# pavapro3c.net
KiCad netlist of a schematic drawn in EAGLE
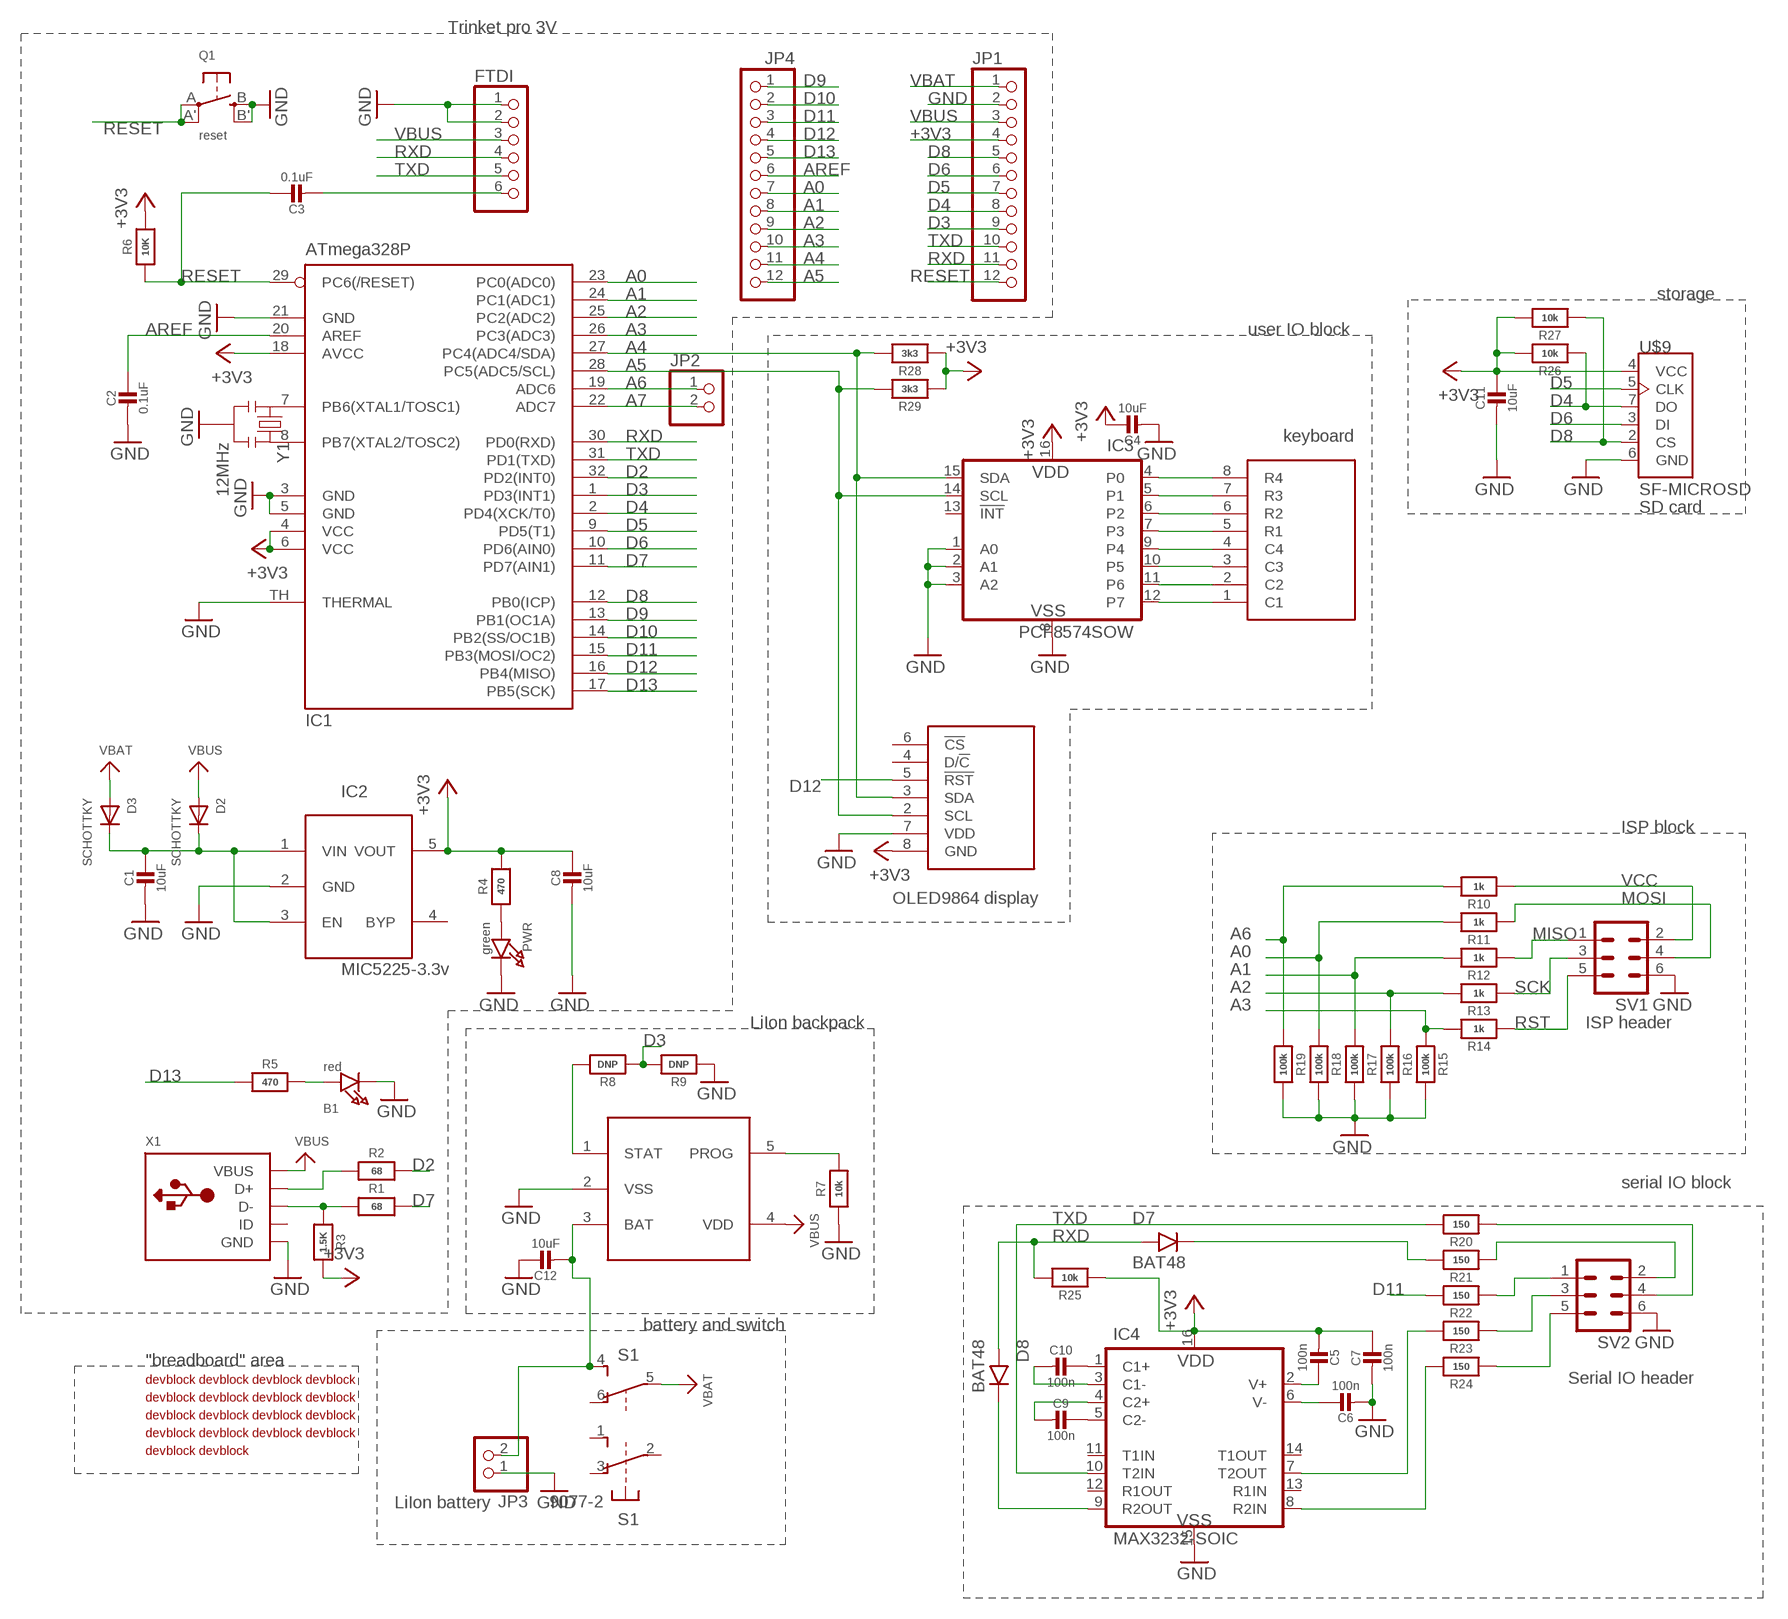
[diagram p0: schematic, sheet 1]

(export (version "E")
  (design (tool "Eeschema 10.0.6"))
  (components
    (comp (ref "B1")
      (value "red")
      (footprint "eagle-import:CHIPLED_0805_NOOUTLINE")
      (libsource (lib "eagle-import") (part "LED0805_NOOUTLINE"))
    )
    (comp (ref "C1")
      (value "10uF")
      (footprint "eagle-import:0805-NO")
      (libsource (lib "eagle-import") (part "CAP_CERAMIC0805-NOOUTLINE"))
    )
    (comp (ref "C2")
      (value "0.1uF")
      (footprint "eagle-import:_0805MP")
      (libsource (lib "eagle-import") (part "CAP_CERAMIC_0805MP"))
    )
    (comp (ref "C3")
      (value "0.1uF")
      (footprint "eagle-import:0805-NO")
      (libsource (lib "eagle-import") (part "CAP_CERAMIC0805-NOOUTLINE"))
    )
    (comp (ref "C4")
      (value "10uF")
      (footprint "eagle-import:0805-NO")
      (libsource (lib "eagle-import") (part "CAP_CERAMIC0805-NOOUTLINE"))
    )
    (comp (ref "C5")
      (value "100n")
      (footprint "eagle-import:0805-NO")
      (libsource (lib "eagle-import") (part "CAP_CERAMIC0805-NOOUTLINE"))
    )
    (comp (ref "C6")
      (value "100n")
      (footprint "eagle-import:0805-NO")
      (libsource (lib "eagle-import") (part "CAP_CERAMIC0805-NOOUTLINE"))
    )
    (comp (ref "C7")
      (value "100n")
      (footprint "eagle-import:0805-NO")
      (libsource (lib "eagle-import") (part "CAP_CERAMIC0805-NOOUTLINE"))
    )
    (comp (ref "C8")
      (value "10uF")
      (footprint "eagle-import:0805-NO")
      (libsource (lib "eagle-import") (part "CAP_CERAMIC0805-NOOUTLINE"))
    )
    (comp (ref "C9")
      (value "100n")
      (footprint "eagle-import:0805-NO")
      (libsource (lib "eagle-import") (part "CAP_CERAMIC0805-NOOUTLINE"))
    )
    (comp (ref "C10")
      (value "100n")
      (footprint "eagle-import:0805-NO")
      (libsource (lib "eagle-import") (part "CAP_CERAMIC0805-NOOUTLINE"))
    )
    (comp (ref "C11")
      (value "10uF")
      (footprint "eagle-import:0805-NO")
      (libsource (lib "eagle-import") (part "CAP_CERAMIC0805-NOOUTLINE"))
    )
    (comp (ref "C12")
      (value "10uF")
      (footprint "eagle-import:0805-NO")
      (libsource (lib "eagle-import") (part "CAP_CERAMIC0805-NOOUTLINE"))
    )
    (comp (ref "D2")
      (value "SCHOTTKY")
      (footprint "eagle-import:ADAFRUIT_SOD-123FL")
      (libsource (lib "eagle-import") (part "ADAFRUIT_DIODE_SOD-123FL"))
    )
    (comp (ref "D3")
      (value "SCHOTTKY")
      (footprint "eagle-import:ADAFRUIT_SOD-123FL")
      (libsource (lib "eagle-import") (part "ADAFRUIT_DIODE_SOD-123FL"))
    )
    (comp (ref "D7")
      (value "BAT48")
      (footprint "eagle-import:SOD-80")
      (libsource (lib "eagle-import") (part "1N4148SOD"))
    )
    (comp (ref "D8")
      (value "BAT48")
      (footprint "eagle-import:SOD-80")
      (libsource (lib "eagle-import") (part "1N4148SOD"))
    )
    (comp (ref "FTDI")
      (value "ADAFRUIT_PINHD-1X6CB")
      (footprint "eagle-import:ADAFRUIT_1X06-CLEANBIG")
      (libsource (lib "eagle-import") (part "ADAFRUIT_PINHD-1X6CB"))
    )
    (comp (ref "IC1")
      (value "ATmega328P")
      (footprint "eagle-import:MLF32-TH")
      (fields (field (name "MPN") "ATMEGA88PA-MU"))
      (libsource (lib "eagle-import") (part "MEGA8-MI"))
    )
    (comp (ref "IC2")
      (value "MIC5225-3.3v")
      (footprint "eagle-import:SOT23-5L")
      (libsource (lib "eagle-import") (part "LP298XS"))
    )
    (comp (ref "IC3")
      (value "PCF8574SOW")
      (footprint "eagle-import:SO-16DW")
      (libsource (lib "eagle-import") (part "PCF8574SOW"))
    )
    (comp (ref "IC4")
      (value "MAX3232-SOIC")
      (footprint "eagle-import:SO-16")
      (libsource (lib "eagle-import") (part "MAX3232-SOIC"))
    )
    (comp (ref "JP1")
      (value "ADAFRUIT_PINHD-1X12-CB")
      (footprint "eagle-import:ADAFRUIT_1X12-CB")
      (libsource (lib "eagle-import") (part "ADAFRUIT_PINHD-1X12-CB"))
    )
    (comp (ref "JP2")
      (value "HEADER-1X2ROUND")
      (footprint "eagle-import:1X02_ROUND")
      (libsource (lib "eagle-import") (part "HEADER-1X2ROUND"))
    )
    (comp (ref "JP3")
      (value "PINHD-1X02_2.54-90°")
      (footprint "eagle-import:1X02_90")
      (libsource (lib "eagle-import") (part "PINHD-1X02_2.54-90°"))
    )
    (comp (ref "JP4")
      (value "ADAFRUIT_PINHD-1X12-CB")
      (footprint "eagle-import:ADAFRUIT_1X12-CB")
      (libsource (lib "eagle-import") (part "ADAFRUIT_PINHD-1X12-CB"))
    )
    (comp (ref "PWR")
      (value "green")
      (footprint "eagle-import:CHIPLED_0805_NOOUTLINE")
      (libsource (lib "eagle-import") (part "LED0805_NOOUTLINE"))
    )
    (comp (ref "Q1")
      (value "reset")
      (footprint "eagle-import:BTN_KMR2_4.6X2.8")
      (libsource (lib "eagle-import") (part "SWITCH_TACT_SMT4.6X2.8"))
    )
    (comp (ref "R1")
      (value "68")
      (footprint "eagle-import:0603-NO")
      (libsource (lib "eagle-import") (part "RESISTOR_0603_NOOUT"))
    )
    (comp (ref "R2")
      (value "68")
      (footprint "eagle-import:0603-NO")
      (libsource (lib "eagle-import") (part "RESISTOR_0603_NOOUT"))
    )
    (comp (ref "R3")
      (value "1.5K")
      (footprint "eagle-import:0603-NO")
      (libsource (lib "eagle-import") (part "RESISTOR_0603_NOOUT"))
    )
    (comp (ref "R4")
      (value "470")
      (footprint "eagle-import:0603-NO")
      (libsource (lib "eagle-import") (part "RESISTOR_0603_NOOUT"))
    )
    (comp (ref "R5")
      (value "470")
      (footprint "eagle-import:0603-NO")
      (libsource (lib "eagle-import") (part "RESISTOR_0603_NOOUT"))
    )
    (comp (ref "R6")
      (value "10K")
      (footprint "eagle-import:0805-NO")
      (libsource (lib "eagle-import") (part "RESISTOR0805_NOOUTLINE"))
    )
    (comp (ref "R7")
      (value "10k")
      (footprint "eagle-import:_0805")
      (libsource (lib "eagle-import") (part "RESISTOR_0805"))
    )
    (comp (ref "R8")
      (value "DNP")
      (footprint "eagle-import:_0805")
      (libsource (lib "eagle-import") (part "RESISTOR_0805"))
    )
    (comp (ref "R9")
      (value "DNP")
      (footprint "eagle-import:_0805")
      (libsource (lib "eagle-import") (part "RESISTOR_0805"))
    )
    (comp (ref "R10")
      (value "1k")
      (footprint "eagle-import:_0805")
      (libsource (lib "eagle-import") (part "RESISTOR_0805"))
    )
    (comp (ref "R11")
      (value "1k")
      (footprint "eagle-import:_0805")
      (libsource (lib "eagle-import") (part "RESISTOR_0805"))
    )
    (comp (ref "R12")
      (value "1k")
      (footprint "eagle-import:_0805")
      (libsource (lib "eagle-import") (part "RESISTOR_0805"))
    )
    (comp (ref "R13")
      (value "1k")
      (footprint "eagle-import:_0805")
      (libsource (lib "eagle-import") (part "RESISTOR_0805"))
    )
    (comp (ref "R14")
      (value "1k")
      (footprint "eagle-import:_0805")
      (libsource (lib "eagle-import") (part "RESISTOR_0805"))
    )
    (comp (ref "R15")
      (value "100k")
      (footprint "eagle-import:_0805")
      (libsource (lib "eagle-import") (part "RESISTOR_0805"))
    )
    (comp (ref "R16")
      (value "100k")
      (footprint "eagle-import:_0805")
      (libsource (lib "eagle-import") (part "RESISTOR_0805"))
    )
    (comp (ref "R17")
      (value "100k")
      (footprint "eagle-import:_0805")
      (libsource (lib "eagle-import") (part "RESISTOR_0805"))
    )
    (comp (ref "R18")
      (value "100k")
      (footprint "eagle-import:_0805")
      (libsource (lib "eagle-import") (part "RESISTOR_0805"))
    )
    (comp (ref "R19")
      (value "100k")
      (footprint "eagle-import:_0805")
      (libsource (lib "eagle-import") (part "RESISTOR_0805"))
    )
    (comp (ref "R20")
      (value "150")
      (footprint "eagle-import:_0805")
      (libsource (lib "eagle-import") (part "RESISTOR_0805"))
    )
    (comp (ref "R21")
      (value "150")
      (footprint "eagle-import:_0805")
      (libsource (lib "eagle-import") (part "RESISTOR_0805"))
    )
    (comp (ref "R22")
      (value "150")
      (footprint "eagle-import:_0805")
      (libsource (lib "eagle-import") (part "RESISTOR_0805"))
    )
    (comp (ref "R23")
      (value "150")
      (footprint "eagle-import:_0805")
      (libsource (lib "eagle-import") (part "RESISTOR_0805"))
    )
    (comp (ref "R24")
      (value "150")
      (footprint "eagle-import:_0805")
      (libsource (lib "eagle-import") (part "RESISTOR_0805"))
    )
    (comp (ref "R25")
      (value "10k")
      (footprint "eagle-import:_0805")
      (libsource (lib "eagle-import") (part "RESISTOR_0805"))
    )
    (comp (ref "R26")
      (value "10k")
      (footprint "eagle-import:_0805")
      (libsource (lib "eagle-import") (part "RESISTOR_0805"))
    )
    (comp (ref "R27")
      (value "10k")
      (footprint "eagle-import:_0805")
      (libsource (lib "eagle-import") (part "RESISTOR_0805"))
    )
    (comp (ref "R28")
      (value "3k3")
      (footprint "eagle-import:_0805")
      (libsource (lib "eagle-import") (part "RESISTOR_0805"))
    )
    (comp (ref "R29")
      (value "3k3")
      (footprint "eagle-import:_0805")
      (libsource (lib "eagle-import") (part "RESISTOR_0805"))
    )
    (comp (ref "S1")
      (value "9077-2")
      (footprint "eagle-import:9077-2")
      (libsource (lib "eagle-import") (part "9077-2"))
    )
    (comp (ref "SV1")
      (value "ML6")
      (footprint "eagle-import:ML6")
      (libsource (lib "eagle-import") (part "ML6"))
    )
    (comp (ref "SV2")
      (value "ML6")
      (footprint "eagle-import:ML6")
      (libsource (lib "eagle-import") (part "ML6"))
    )
    (comp (ref "U$5")
      (value "DISP_OLED_2864")
      (footprint "eagle-import:OLED2864")
      (libsource (lib "eagle-import") (part "DISP_OLED_2864"))
    )
    (comp (ref "U$6")
      (value "MCP73831")
      (footprint "eagle-import:SOT23-5")
      (libsource (lib "eagle-import") (part "MCP73831"))
    )
    (comp (ref "U$7")
      (value "KB1604")
      (footprint "eagle-import:KB1604")
      (libsource (lib "eagle-import") (part "KB1604"))
    )
    (comp (ref "U$9")
      (value "SF-MICROSD")
      (footprint "eagle-import:MICROSD")
      (libsource (lib "eagle-import") (part "SF-MICROSD"))
    )
    (comp (ref "U$10")
      (value "DEVBLOCK_1_16")
      (footprint "eagle-import:DEVBLOCK_1_16")
      (libsource (lib "eagle-import") (part "DEVBLOCK_1_16"))
    )
    (comp (ref "U$11")
      (value "DEVBLOCK_1_16")
      (footprint "eagle-import:DEVBLOCK_1_16")
      (libsource (lib "eagle-import") (part "DEVBLOCK_1_16"))
    )
    (comp (ref "U$12")
      (value "DEVBLOCK_1_16")
      (footprint "eagle-import:DEVBLOCK_1_16")
      (libsource (lib "eagle-import") (part "DEVBLOCK_1_16"))
    )
    (comp (ref "U$13")
      (value "DEVBLOCK_1_16")
      (footprint "eagle-import:DEVBLOCK_1_16")
      (libsource (lib "eagle-import") (part "DEVBLOCK_1_16"))
    )
    (comp (ref "U$14")
      (value "DEVBLOCK_1_16")
      (footprint "eagle-import:DEVBLOCK_1_16")
      (libsource (lib "eagle-import") (part "DEVBLOCK_1_16"))
    )
    (comp (ref "U$15")
      (value "DEVBLOCK_1_16")
      (footprint "eagle-import:DEVBLOCK_1_16")
      (libsource (lib "eagle-import") (part "DEVBLOCK_1_16"))
    )
    (comp (ref "U$16")
      (value "DEVBLOCK_1_16")
      (footprint "eagle-import:DEVBLOCK_1_16")
      (libsource (lib "eagle-import") (part "DEVBLOCK_1_16"))
    )
    (comp (ref "U$17")
      (value "DEVBLOCK_1_16")
      (footprint "eagle-import:DEVBLOCK_1_16")
      (libsource (lib "eagle-import") (part "DEVBLOCK_1_16"))
    )
    (comp (ref "U$18")
      (value "DEVBLOCK_1_16")
      (footprint "eagle-import:DEVBLOCK_1_16")
      (libsource (lib "eagle-import") (part "DEVBLOCK_1_16"))
    )
    (comp (ref "U$19")
      (value "DEVBLOCK_1_16")
      (footprint "eagle-import:DEVBLOCK_1_16")
      (libsource (lib "eagle-import") (part "DEVBLOCK_1_16"))
    )
    (comp (ref "U$20")
      (value "DEVBLOCK_1_16")
      (footprint "eagle-import:DEVBLOCK_1_16")
      (libsource (lib "eagle-import") (part "DEVBLOCK_1_16"))
    )
    (comp (ref "U$21")
      (value "DEVBLOCK_1_16")
      (footprint "eagle-import:DEVBLOCK_1_16")
      (libsource (lib "eagle-import") (part "DEVBLOCK_1_16"))
    )
    (comp (ref "U$22")
      (value "DEVBLOCK_1_16")
      (footprint "eagle-import:DEVBLOCK_1_16")
      (libsource (lib "eagle-import") (part "DEVBLOCK_1_16"))
    )
    (comp (ref "U$23")
      (value "DEVBLOCK_1_16")
      (footprint "eagle-import:DEVBLOCK_1_16")
      (libsource (lib "eagle-import") (part "DEVBLOCK_1_16"))
    )
    (comp (ref "U$24")
      (value "DEVBLOCK_1_16")
      (footprint "eagle-import:DEVBLOCK_1_16")
      (libsource (lib "eagle-import") (part "DEVBLOCK_1_16"))
    )
    (comp (ref "U$25")
      (value "DEVBLOCK_1_16")
      (footprint "eagle-import:DEVBLOCK_1_16")
      (libsource (lib "eagle-import") (part "DEVBLOCK_1_16"))
    )
    (comp (ref "U$26")
      (value "DEVBLOCK_1_16")
      (footprint "eagle-import:DEVBLOCK_1_16")
      (libsource (lib "eagle-import") (part "DEVBLOCK_1_16"))
    )
    (comp (ref "U$27")
      (value "DEVBLOCK_1_16")
      (footprint "eagle-import:DEVBLOCK_1_16")
      (libsource (lib "eagle-import") (part "DEVBLOCK_1_16"))
    )
    (comp (ref "X1")
      (value "MICROBUILDER_USBMICRO_20329")
      (footprint "eagle-import:MICROBUILDER_4UCONN_20329")
      (libsource (lib "eagle-import") (part "MICROBUILDER_USBMICRO_20329"))
    )
    (comp (ref "Y1")
      (value "12MHz")
      (footprint "eagle-import:RESONATOR-SMD")
      (libsource (lib "eagle-import") (part "RESONATORSMD"))
    )
  )
  (nets
    (net (code "1") (name "+3V3") (class "Default")
      (node (ref "C11") (pin "1") (pinfunction "1_1") (pintype "passive"))
      (node (ref "C4") (pin "1") (pinfunction "1_1") (pintype "passive"))
      (node (ref "C5") (pin "2") (pinfunction "2_2") (pintype "passive"))
      (node (ref "C7") (pin "1") (pinfunction "1_1") (pintype "passive"))
      (node (ref "C8") (pin "1") (pinfunction "1_1") (pintype "passive"))
      (node (ref "IC1") (pin "18") (pinfunction "AVCC_18") (pintype "power_in"))
      (node (ref "IC1") (pin "4") (pinfunction "VCC_4") (pintype "power_in"))
      (node (ref "IC1") (pin "6") (pinfunction "VCC_6") (pintype "power_in"))
      (node (ref "IC2") (pin "5") (pinfunction "VOUT_5") (pintype "bidirectional"))
      (node (ref "IC3") (pin "16") (pinfunction "VDD_16") (pintype "power_in"))
      (node (ref "IC4") (pin "16") (pinfunction "VDD_16") (pintype "power_in"))
      (node (ref "JP1") (pin "4") (pinfunction "4_4") (pintype "passive"))
      (node (ref "R25") (pin "2") (pinfunction "2_2") (pintype "passive"))
      (node (ref "R26") (pin "1") (pinfunction "1_1") (pintype "passive"))
      (node (ref "R27") (pin "1") (pinfunction "1_1") (pintype "passive"))
      (node (ref "R28") (pin "2") (pinfunction "2_2") (pintype "passive"))
      (node (ref "R29") (pin "2") (pinfunction "2_2") (pintype "passive"))
      (node (ref "R3") (pin "2") (pinfunction "2_2") (pintype "passive"))
      (node (ref "R4") (pin "2") (pinfunction "2_2") (pintype "passive"))
      (node (ref "R6") (pin "2") (pinfunction "2_2") (pintype "passive"))
      (node (ref "U$5") (pin "8") (pinfunction "GND_8") (pintype "bidirectional"))
      (node (ref "U$9") (pin "4") (pinfunction "VCC_4") (pintype "passive"))
    )
    (net (code "2") (name "/A0") (class "Default")
      (node (ref "IC1") (pin "23") (pinfunction "PC0(ADC0)_23") (pintype "bidirectional"))
      (node (ref "JP4") (pin "7") (pinfunction "7_7") (pintype "passive"))
      (node (ref "R11") (pin "1") (pinfunction "1_1") (pintype "passive"))
      (node (ref "R18") (pin "2") (pinfunction "2_2") (pintype "passive"))
    )
    (net (code "3") (name "/A1") (class "Default")
      (node (ref "IC1") (pin "24") (pinfunction "PC1(ADC1)_24") (pintype "bidirectional"))
      (node (ref "JP4") (pin "8") (pinfunction "8_8") (pintype "passive"))
      (node (ref "R12") (pin "1") (pinfunction "1_1") (pintype "passive"))
      (node (ref "R17") (pin "2") (pinfunction "2_2") (pintype "passive"))
    )
    (net (code "4") (name "/A2") (class "Default")
      (node (ref "IC1") (pin "25") (pinfunction "PC2(ADC2)_25") (pintype "bidirectional"))
      (node (ref "JP4") (pin "9") (pinfunction "9_9") (pintype "passive"))
      (node (ref "R13") (pin "1") (pinfunction "1_1") (pintype "passive"))
      (node (ref "R16") (pin "2") (pinfunction "2_2") (pintype "passive"))
    )
    (net (code "5") (name "/A3") (class "Default")
      (node (ref "IC1") (pin "26") (pinfunction "PC3(ADC3)_26") (pintype "bidirectional"))
      (node (ref "JP4") (pin "10") (pinfunction "10_10") (pintype "passive"))
      (node (ref "R14") (pin "1") (pinfunction "1_1") (pintype "passive"))
      (node (ref "R15") (pin "2") (pinfunction "2_2") (pintype "passive"))
    )
    (net (code "6") (name "/A4") (class "Default")
      (node (ref "IC1") (pin "27") (pinfunction "PC4(ADC4/SDA)_27") (pintype "bidirectional"))
      (node (ref "IC3") (pin "15") (pinfunction "SDA_15") (pintype "bidirectional"))
      (node (ref "JP4") (pin "11") (pinfunction "11_11") (pintype "passive"))
      (node (ref "R28") (pin "1") (pinfunction "1_1") (pintype "passive"))
      (node (ref "U$5") (pin "3") (pinfunction "SDA_3") (pintype "bidirectional"))
    )
    (net (code "7") (name "/A5") (class "Default")
      (node (ref "IC1") (pin "28") (pinfunction "PC5(ADC5/SCL)_28") (pintype "bidirectional"))
      (node (ref "IC3") (pin "14") (pinfunction "SCL_14") (pintype "bidirectional"))
      (node (ref "JP4") (pin "12") (pinfunction "12_12") (pintype "passive"))
      (node (ref "R29") (pin "1") (pinfunction "1_1") (pintype "passive"))
      (node (ref "U$5") (pin "2") (pinfunction "SCL_2") (pintype "bidirectional"))
    )
    (net (code "8") (name "/A6") (class "Default")
      (node (ref "IC1") (pin "19") (pinfunction "ADC6_19") (pintype "bidirectional"))
      (node (ref "JP2") (pin "1") (pinfunction "1_1") (pintype "passive"))
      (node (ref "R10") (pin "1") (pinfunction "1_1") (pintype "passive"))
      (node (ref "R19") (pin "2") (pinfunction "2_2") (pintype "passive"))
    )
    (net (code "9") (name "/A7") (class "Default")
      (node (ref "IC1") (pin "22") (pinfunction "ADC7_22") (pintype "bidirectional"))
      (node (ref "JP2") (pin "2") (pinfunction "2_2") (pintype "passive"))
    )
    (net (code "10") (name "/AREF") (class "Default")
      (node (ref "C2") (pin "1") (pinfunction "1_1") (pintype "passive"))
      (node (ref "IC1") (pin "20") (pinfunction "AREF_20") (pintype "passive"))
      (node (ref "JP4") (pin "6") (pinfunction "6_6") (pintype "passive"))
    )
    (net (code "11") (name "/D2") (class "Default")
      (node (ref "IC1") (pin "32") (pinfunction "PD2(INT0)_32") (pintype "bidirectional"))
      (node (ref "R2") (pin "2") (pinfunction "2_2") (pintype "passive"))
    )
    (net (code "12") (name "/D3") (class "Default")
      (node (ref "IC1") (pin "1") (pinfunction "PD3(INT1)_1") (pintype "bidirectional"))
      (node (ref "JP1") (pin "9") (pinfunction "9_9") (pintype "passive"))
      (node (ref "R8") (pin "2") (pinfunction "2_2") (pintype "passive"))
      (node (ref "R9") (pin "1") (pinfunction "1_1") (pintype "passive"))
    )
    (net (code "13") (name "/D4") (class "Default")
      (node (ref "IC1") (pin "2") (pinfunction "PD4(XCK/T0)_2") (pintype "bidirectional"))
      (node (ref "JP1") (pin "8") (pinfunction "8_8") (pintype "passive"))
      (node (ref "R26") (pin "2") (pinfunction "2_2") (pintype "passive"))
      (node (ref "U$9") (pin "7") (pinfunction "DO_7") (pintype "bidirectional"))
    )
    (net (code "14") (name "/D5") (class "Default")
      (node (ref "IC1") (pin "9") (pinfunction "PD5(T1)_9") (pintype "bidirectional"))
      (node (ref "JP1") (pin "7") (pinfunction "7_7") (pintype "passive"))
      (node (ref "U$9") (pin "5") (pinfunction "CLK_5") (pintype "bidirectional"))
    )
    (net (code "15") (name "/D6") (class "Default")
      (node (ref "IC1") (pin "10") (pinfunction "PD6(AIN0)_10") (pintype "bidirectional"))
      (node (ref "JP1") (pin "6") (pinfunction "6_6") (pintype "passive"))
      (node (ref "U$9") (pin "3") (pinfunction "DI_3") (pintype "bidirectional"))
    )
    (net (code "16") (name "/D7") (class "Default")
      (node (ref "IC1") (pin "11") (pinfunction "PD7(AIN1)_11") (pintype "bidirectional"))
      (node (ref "R1") (pin "2") (pinfunction "2_2") (pintype "passive"))
    )
    (net (code "17") (name "/D8") (class "Default")
      (node (ref "IC1") (pin "12") (pinfunction "PB0(ICP)_12") (pintype "bidirectional"))
      (node (ref "JP1") (pin "5") (pinfunction "5_5") (pintype "passive"))
      (node (ref "R27") (pin "2") (pinfunction "2_2") (pintype "passive"))
      (node (ref "U$9") (pin "2") (pinfunction "CS_2") (pintype "bidirectional"))
    )
    (net (code "18") (name "/D9") (class "Default")
      (node (ref "IC1") (pin "13") (pinfunction "PB1(OC1A)_13") (pintype "bidirectional"))
      (node (ref "JP4") (pin "1") (pinfunction "1_1") (pintype "passive"))
    )
    (net (code "19") (name "/D10") (class "Default")
      (node (ref "IC1") (pin "14") (pinfunction "PB2(SS/OC1B)_14") (pintype "bidirectional"))
      (node (ref "JP4") (pin "2") (pinfunction "2_2") (pintype "passive"))
    )
    (net (code "20") (name "/D11") (class "Default")
      (node (ref "IC1") (pin "15") (pinfunction "PB3(MOSI/OC2)_15") (pintype "bidirectional"))
      (node (ref "JP4") (pin "3") (pinfunction "3_3") (pintype "passive"))
      (node (ref "R22") (pin "1") (pinfunction "1_1") (pintype "passive"))
    )
    (net (code "21") (name "/D12") (class "Default")
      (node (ref "IC1") (pin "16") (pinfunction "PB4(MISO)_16") (pintype "bidirectional"))
      (node (ref "JP4") (pin "4") (pinfunction "4_4") (pintype "passive"))
      (node (ref "U$5") (pin "5") (pinfunction "~{RST}_5") (pintype "bidirectional"))
    )
    (net (code "22") (name "/D13") (class "Default")
      (node (ref "IC1") (pin "17") (pinfunction "PB5(SCK)_17") (pintype "bidirectional"))
      (node (ref "JP4") (pin "5") (pinfunction "5_5") (pintype "passive"))
      (node (ref "R5") (pin "2") (pinfunction "2_2") (pintype "passive"))
    )
    (net (code "23") (name "/MISO") (class "Default")
      (node (ref "R12") (pin "2") (pinfunction "2_2") (pintype "passive"))
      (node (ref "SV1") (pin "1") (pinfunction "1_1") (pintype "passive"))
    )
    (net (code "24") (name "/MOSI") (class "Default")
      (node (ref "R11") (pin "2") (pinfunction "2_2") (pintype "passive"))
      (node (ref "SV1") (pin "4") (pinfunction "4_4") (pintype "passive"))
    )
    (net (code "25") (name "/RESET") (class "Default")
      (node (ref "C3") (pin "1") (pinfunction "1_1") (pintype "passive"))
      (node (ref "IC1") (pin "29") (pinfunction "PC6(/RESET)_29") (pintype "bidirectional"))
      (node (ref "JP1") (pin "12") (pinfunction "12_12") (pintype "passive"))
      (node (ref "Q1") (pin "A") (pinfunction "P_A") (pintype "passive"))
      (node (ref "Q1") (pin "A'") (pinfunction "P1_A'") (pintype "passive"))
      (node (ref "R6") (pin "1") (pinfunction "1_1") (pintype "passive"))
    )
    (net (code "26") (name "/RST") (class "Default")
      (node (ref "R14") (pin "2") (pinfunction "2_2") (pintype "passive"))
      (node (ref "SV1") (pin "5") (pinfunction "5_5") (pintype "passive"))
    )
    (net (code "27") (name "/RXD") (class "Default")
      (node (ref "D7") (pin "A") (pinfunction "A_A") (pintype "input"))
      (node (ref "D8") (pin "A") (pinfunction "A_A") (pintype "input"))
      (node (ref "FTDI") (pin "4") (pinfunction "4_4") (pintype "passive"))
      (node (ref "IC1") (pin "30") (pinfunction "PD0(RXD)_30") (pintype "bidirectional"))
      (node (ref "JP1") (pin "11") (pinfunction "11_11") (pintype "passive"))
      (node (ref "R25") (pin "1") (pinfunction "1_1") (pintype "passive"))
    )
    (net (code "28") (name "/SCK") (class "Default")
      (node (ref "R13") (pin "2") (pinfunction "2_2") (pintype "passive"))
      (node (ref "SV1") (pin "3") (pinfunction "3_3") (pintype "passive"))
    )
    (net (code "29") (name "/TXD") (class "Default")
      (node (ref "FTDI") (pin "5") (pinfunction "5_5") (pintype "passive"))
      (node (ref "IC1") (pin "31") (pinfunction "PD1(TXD)_31") (pintype "bidirectional"))
      (node (ref "IC4") (pin "10") (pinfunction "T2IN_10") (pintype "input"))
      (node (ref "JP1") (pin "10") (pinfunction "10_10") (pintype "passive"))
      (node (ref "R20") (pin "1") (pinfunction "1_1") (pintype "passive"))
    )
    (net (code "30") (name "/VCC") (class "Default")
      (node (ref "R10") (pin "2") (pinfunction "2_2") (pintype "passive"))
      (node (ref "SV1") (pin "2") (pinfunction "2_2") (pintype "passive"))
    )
    (net (code "31") (name "GND") (class "Default")
      (node (ref "B1") (pin "C") (pinfunction "C_C") (pintype "passive"))
      (node (ref "C1") (pin "2") (pinfunction "2_2") (pintype "passive"))
      (node (ref "C11") (pin "2") (pinfunction "2_2") (pintype "passive"))
      (node (ref "C12") (pin "1") (pinfunction "1_1") (pintype "passive"))
      (node (ref "C2") (pin "2") (pinfunction "2_2") (pintype "passive"))
      (node (ref "C4") (pin "2") (pinfunction "2_2") (pintype "passive"))
      (node (ref "C6") (pin "2") (pinfunction "2_2") (pintype "passive"))
      (node (ref "C7") (pin "2") (pinfunction "2_2") (pintype "passive"))
      (node (ref "C8") (pin "2") (pinfunction "2_2") (pintype "passive"))
      (node (ref "FTDI") (pin "1") (pinfunction "1_1") (pintype "passive"))
      (node (ref "FTDI") (pin "2") (pinfunction "2_2") (pintype "passive"))
      (node (ref "IC1") (pin "21") (pinfunction "GND_21") (pintype "power_in"))
      (node (ref "IC1") (pin "3") (pinfunction "GND_3") (pintype "power_in"))
      (node (ref "IC1") (pin "5") (pinfunction "GND_5") (pintype "power_in"))
      (node (ref "IC1") (pin "TH") (pinfunction "THERMAL_TH") (pintype "passive"))
      (node (ref "IC2") (pin "2") (pinfunction "GND_2") (pintype "bidirectional"))
      (node (ref "IC3") (pin "1") (pinfunction "A0_1") (pintype "bidirectional"))
      (node (ref "IC3") (pin "2") (pinfunction "A1_2") (pintype "bidirectional"))
      (node (ref "IC3") (pin "3") (pinfunction "A2_3") (pintype "bidirectional"))
      (node (ref "IC3") (pin "8") (pinfunction "VSS_8") (pintype "power_in"))
      (node (ref "IC4") (pin "15") (pinfunction "VSS_15") (pintype "power_in"))
      (node (ref "JP1") (pin "2") (pinfunction "2_2") (pintype "passive"))
      (node (ref "JP3") (pin "1") (pinfunction "1_1") (pintype "passive"))
      (node (ref "PWR") (pin "C") (pinfunction "C_C") (pintype "passive"))
      (node (ref "Q1") (pin "B") (pinfunction "S_B") (pintype "passive"))
      (node (ref "Q1") (pin "B'") (pinfunction "S1_B'") (pintype "passive"))
      (node (ref "R15") (pin "1") (pinfunction "1_1") (pintype "passive"))
      (node (ref "R16") (pin "1") (pinfunction "1_1") (pintype "passive"))
      (node (ref "R17") (pin "1") (pinfunction "1_1") (pintype "passive"))
      (node (ref "R18") (pin "1") (pinfunction "1_1") (pintype "passive"))
      (node (ref "R19") (pin "1") (pinfunction "1_1") (pintype "passive"))
      (node (ref "R7") (pin "2") (pinfunction "2_2") (pintype "passive"))
      (node (ref "R9") (pin "2") (pinfunction "2_2") (pintype "passive"))
      (node (ref "SV1") (pin "6") (pinfunction "6_6") (pintype "passive"))
      (node (ref "SV2") (pin "6") (pinfunction "6_6") (pintype "passive"))
      (node (ref "U$5") (pin "7") (pinfunction "VDD_7") (pintype "bidirectional"))
      (node (ref "U$6") (pin "2") (pinfunction "VSS_2") (pintype "bidirectional"))
      (node (ref "U$9") (pin "6") (pinfunction "GND_6") (pintype "power_in"))
      (node (ref "X1") (pin "BASE@1") (pinfunction "GND_BASE@1") (pintype "power_in"))
      (node (ref "X1") (pin "BASE@2") (pinfunction "GND_BASE@2") (pintype "power_in"))
      (node (ref "X1") (pin "GND") (pinfunction "GND_GND") (pintype "power_in"))
      (node (ref "X1") (pin "SPRT@1") (pinfunction "GND_SPRT@1") (pintype "power_in"))
      (node (ref "X1") (pin "SPRT@2") (pinfunction "GND_SPRT@2") (pintype "power_in"))
      (node (ref "X1") (pin "SPRT@3") (pinfunction "GND_SPRT@3") (pintype "power_in"))
      (node (ref "X1") (pin "SPRT@4") (pinfunction "GND_SPRT@4") (pintype "power_in"))
      (node (ref "Y1") (pin "2") (pinfunction "2_2") (pintype "passive"))
    )
    (net (code "32") (name "Net-(B1-PadA)") (class "Default")
      (node (ref "B1") (pin "A") (pinfunction "A_A") (pintype "passive"))
      (node (ref "R5") (pin "1") (pinfunction "1_1") (pintype "passive"))
    )
    (net (code "33") (name "Net-(C3-Pad2)") (class "Default")
      (node (ref "C3") (pin "2") (pinfunction "2_2") (pintype "passive"))
      (node (ref "FTDI") (pin "6") (pinfunction "6_6") (pintype "passive"))
    )
    (net (code "34") (name "Net-(D7-PadK)") (class "Default")
      (node (ref "D7") (pin "K") (pinfunction "K_K") (pintype "output"))
      (node (ref "R21") (pin "1") (pinfunction "1_1") (pintype "passive"))
    )
    (net (code "35") (name "Net-(IC1-PB6(XTAL1{slash}TOSC1))") (class "Default")
      (node (ref "IC1") (pin "7") (pinfunction "PB6(XTAL1/TOSC1)_7") (pintype "bidirectional"))
      (node (ref "Y1") (pin "1") (pinfunction "1_1") (pintype "passive"))
    )
    (net (code "36") (name "Net-(IC1-PB7(XTAL2{slash}TOSC2))") (class "Default")
      (node (ref "IC1") (pin "8") (pinfunction "PB7(XTAL2/TOSC2)_8") (pintype "bidirectional"))
      (node (ref "Y1") (pin "3") (pinfunction "3_3") (pintype "passive"))
    )
    (net (code "37") (name "Net-(IC2-EN)") (class "Default")
      (node (ref "C1") (pin "1") (pinfunction "1_1") (pintype "passive"))
      (node (ref "D2") (pin "C") (pinfunction "C_C") (pintype "passive"))
      (node (ref "D3") (pin "C") (pinfunction "C_C") (pintype "passive"))
      (node (ref "IC2") (pin "1") (pinfunction "VIN_1") (pintype "bidirectional"))
      (node (ref "IC2") (pin "3") (pinfunction "EN_3") (pintype "bidirectional"))
    )
    (net (code "38") (name "Net-(IC3-P0)") (class "Default")
      (node (ref "IC3") (pin "4") (pinfunction "P0_4") (pintype "bidirectional"))
      (node (ref "U$7") (pin "8") (pinfunction "R4_8") (pintype "bidirectional"))
    )
    (net (code "39") (name "Net-(IC3-P1)") (class "Default")
      (node (ref "IC3") (pin "5") (pinfunction "P1_5") (pintype "bidirectional"))
      (node (ref "U$7") (pin "7") (pinfunction "R3_7") (pintype "bidirectional"))
    )
    (net (code "40") (name "Net-(IC3-P2)") (class "Default")
      (node (ref "IC3") (pin "6") (pinfunction "P2_6") (pintype "bidirectional"))
      (node (ref "U$7") (pin "6") (pinfunction "R2_6") (pintype "bidirectional"))
    )
    (net (code "41") (name "Net-(IC3-P3)") (class "Default")
      (node (ref "IC3") (pin "7") (pinfunction "P3_7") (pintype "bidirectional"))
      (node (ref "U$7") (pin "5") (pinfunction "R1_5") (pintype "bidirectional"))
    )
    (net (code "42") (name "Net-(IC3-P4)") (class "Default")
      (node (ref "IC3") (pin "9") (pinfunction "P4_9") (pintype "bidirectional"))
      (node (ref "U$7") (pin "4") (pinfunction "C4_4") (pintype "bidirectional"))
    )
    (net (code "43") (name "Net-(IC3-P5)") (class "Default")
      (node (ref "IC3") (pin "10") (pinfunction "P5_10") (pintype "bidirectional"))
      (node (ref "U$7") (pin "3") (pinfunction "C3_3") (pintype "bidirectional"))
    )
    (net (code "44") (name "Net-(IC3-P6)") (class "Default")
      (node (ref "IC3") (pin "11") (pinfunction "P6_11") (pintype "bidirectional"))
      (node (ref "U$7") (pin "2") (pinfunction "C2_2") (pintype "bidirectional"))
    )
    (net (code "45") (name "Net-(IC3-P7)") (class "Default")
      (node (ref "IC3") (pin "12") (pinfunction "P7_12") (pintype "bidirectional"))
      (node (ref "U$7") (pin "1") (pinfunction "C1_1") (pintype "bidirectional"))
    )
    (net (code "46") (name "Net-(IC4-C1+)") (class "Default")
      (node (ref "C10") (pin "1") (pinfunction "1_1") (pintype "passive"))
      (node (ref "IC4") (pin "1") (pinfunction "C1+_1") (pintype "bidirectional"))
    )
    (net (code "47") (name "Net-(IC4-C1-)") (class "Default")
      (node (ref "C10") (pin "2") (pinfunction "2_2") (pintype "passive"))
      (node (ref "IC4") (pin "3") (pinfunction "C1-_3") (pintype "bidirectional"))
    )
    (net (code "48") (name "Net-(IC4-C2+)") (class "Default")
      (node (ref "C9") (pin "2") (pinfunction "2_2") (pintype "passive"))
      (node (ref "IC4") (pin "4") (pinfunction "C2+_4") (pintype "bidirectional"))
    )
    (net (code "49") (name "Net-(IC4-C2-)") (class "Default")
      (node (ref "C9") (pin "1") (pinfunction "1_1") (pintype "passive"))
      (node (ref "IC4") (pin "5") (pinfunction "C2-_5") (pintype "bidirectional"))
    )
    (net (code "50") (name "Net-(IC4-R2IN)") (class "Default")
      (node (ref "IC4") (pin "8") (pinfunction "R2IN_8") (pintype "output"))
      (node (ref "R24") (pin "1") (pinfunction "1_1") (pintype "passive"))
    )
    (net (code "51") (name "Net-(IC4-R2OUT)") (class "Default")
      (node (ref "D8") (pin "K") (pinfunction "K_K") (pintype "output"))
      (node (ref "IC4") (pin "9") (pinfunction "R2OUT_9") (pintype "input"))
    )
    (net (code "52") (name "Net-(IC4-T2OUT)") (class "Default")
      (node (ref "IC4") (pin "7") (pinfunction "T2OUT_7") (pintype "output"))
      (node (ref "R23") (pin "1") (pinfunction "1_1") (pintype "passive"))
    )
    (net (code "53") (name "Net-(IC4-V+)") (class "Default")
      (node (ref "C5") (pin "1") (pinfunction "1_1") (pintype "passive"))
      (node (ref "IC4") (pin "2") (pinfunction "V+_2") (pintype "bidirectional"))
    )
    (net (code "54") (name "Net-(IC4-V-)") (class "Default")
      (node (ref "C6") (pin "1") (pinfunction "1_1") (pintype "passive"))
      (node (ref "IC4") (pin "6") (pinfunction "V-_6") (pintype "bidirectional"))
    )
    (net (code "55") (name "Net-(PWR-PadA)") (class "Default")
      (node (ref "PWR") (pin "A") (pinfunction "A_A") (pintype "passive"))
      (node (ref "R4") (pin "1") (pinfunction "1_1") (pintype "passive"))
    )
    (net (code "56") (name "Net-(R1-Pad1)") (class "Default")
      (node (ref "R1") (pin "1") (pinfunction "1_1") (pintype "passive"))
      (node (ref "R3") (pin "1") (pinfunction "1_1") (pintype "passive"))
      (node (ref "X1") (pin "D-") (pinfunction "D-_D-") (pintype "bidirectional"))
    )
    (net (code "57") (name "Net-(R2-Pad1)") (class "Default")
      (node (ref "R2") (pin "1") (pinfunction "1_1") (pintype "passive"))
      (node (ref "X1") (pin "D+") (pinfunction "D+_D+") (pintype "bidirectional"))
    )
    (net (code "58") (name "Net-(R20-Pad2)") (class "Default")
      (node (ref "R20") (pin "2") (pinfunction "2_2") (pintype "passive"))
      (node (ref "SV2") (pin "4") (pinfunction "4_4") (pintype "passive"))
    )
    (net (code "59") (name "Net-(R21-Pad2)") (class "Default")
      (node (ref "R21") (pin "2") (pinfunction "2_2") (pintype "passive"))
      (node (ref "SV2") (pin "2") (pinfunction "2_2") (pintype "passive"))
    )
    (net (code "60") (name "Net-(R22-Pad2)") (class "Default")
      (node (ref "R22") (pin "2") (pinfunction "2_2") (pintype "passive"))
      (node (ref "SV2") (pin "1") (pinfunction "1_1") (pintype "passive"))
    )
    (net (code "61") (name "Net-(R23-Pad2)") (class "Default")
      (node (ref "R23") (pin "2") (pinfunction "2_2") (pintype "passive"))
      (node (ref "SV2") (pin "3") (pinfunction "3_3") (pintype "passive"))
    )
    (net (code "62") (name "Net-(R24-Pad2)") (class "Default")
      (node (ref "R24") (pin "2") (pinfunction "2_2") (pintype "passive"))
      (node (ref "SV2") (pin "5") (pinfunction "5_5") (pintype "passive"))
    )
    (net (code "63") (name "Net-(S1B-S)") (class "Default")
      (node (ref "C12") (pin "2") (pinfunction "2_2") (pintype "passive"))
      (node (ref "JP3") (pin "2") (pinfunction "2_2") (pintype "passive"))
      (node (ref "S1") (pin "4") (pinfunction "S_4") (pintype "passive"))
      (node (ref "U$6") (pin "3") (pinfunction "BAT_3") (pintype "bidirectional"))
    )
    (net (code "64") (name "Net-(U$6-PROG)") (class "Default")
      (node (ref "R7") (pin "1") (pinfunction "1_1") (pintype "passive"))
      (node (ref "U$6") (pin "5") (pinfunction "PROG_5") (pintype "bidirectional"))
    )
    (net (code "65") (name "Net-(U$6-STAT)") (class "Default")
      (node (ref "R8") (pin "1") (pinfunction "1_1") (pintype "passive"))
      (node (ref "U$6") (pin "1") (pinfunction "STAT_1") (pintype "bidirectional"))
    )
    (net (code "66") (name "VBAT") (class "Default")
      (node (ref "D3") (pin "A") (pinfunction "A_A") (pintype "passive"))
      (node (ref "JP1") (pin "1") (pinfunction "1_1") (pintype "passive"))
      (node (ref "S1") (pin "5") (pinfunction "P_5") (pintype "passive"))
    )
    (net (code "67") (name "VBUS") (class "Default")
      (node (ref "D2") (pin "A") (pinfunction "A_A") (pintype "passive"))
      (node (ref "FTDI") (pin "3") (pinfunction "3_3") (pintype "passive"))
      (node (ref "JP1") (pin "3") (pinfunction "3_3") (pintype "passive"))
      (node (ref "U$6") (pin "4") (pinfunction "VDD_4") (pintype "bidirectional"))
      (node (ref "X1") (pin "VBUS") (pinfunction "VBUS_VBUS") (pintype "power_in"))
    )
    (net (code "68") (name "unconnected-(IC2-BYP-Pad4)") (class "Default")
      (node (ref "IC2") (pin "4") (pinfunction "BYP_4") (pintype "bidirectional"))
    )
    (net (code "69") (name "unconnected-(IC3-~{INT}-Pad13)") (class "Default")
      (node (ref "IC3") (pin "13") (pinfunction "~{INT}_13") (pintype "bidirectional"))
    )
    (net (code "70") (name "unconnected-(IC4-R1IN-Pad13)") (class "Default")
      (node (ref "IC4") (pin "13") (pinfunction "R1IN_13") (pintype "output"))
    )
    (net (code "71") (name "unconnected-(IC4-R1OUT-Pad12)") (class "Default")
      (node (ref "IC4") (pin "12") (pinfunction "R1OUT_12") (pintype "input"))
    )
    (net (code "72") (name "unconnected-(IC4-T1IN-Pad11)") (class "Default")
      (node (ref "IC4") (pin "11") (pinfunction "T1IN_11") (pintype "input"))
    )
    (net (code "73") (name "unconnected-(IC4-T1OUT-Pad14)") (class "Default")
      (node (ref "IC4") (pin "14") (pinfunction "T1OUT_14") (pintype "output"))
    )
    (net (code "74") (name "unconnected-(S1A-O-Pad3)") (class "Default")
      (node (ref "S1") (pin "3") (pinfunction "O_3") (pintype "passive"))
    )
    (net (code "75") (name "unconnected-(S1A-P-Pad2)") (class "Default")
      (node (ref "S1") (pin "2") (pinfunction "P_2") (pintype "passive"))
    )
    (net (code "76") (name "unconnected-(S1A-S-Pad1)") (class "Default")
      (node (ref "S1") (pin "1") (pinfunction "S_1") (pintype "passive"))
    )
    (net (code "77") (name "unconnected-(S1B-O-Pad6)") (class "Default")
      (node (ref "S1") (pin "6") (pinfunction "O_6") (pintype "passive"))
    )
    (net (code "78") (name "unconnected-(U$5-D{slash}~{C}-Pad4)") (class "Default")
      (node (ref "U$5") (pin "4") (pinfunction "D/~{C}_4") (pintype "bidirectional"))
    )
    (net (code "79") (name "unconnected-(U$5-~{CS}-Pad6)") (class "Default")
      (node (ref "U$5") (pin "6") (pinfunction "~{CS}_6") (pintype "bidirectional"))
    )
    (net (code "80") (name "unconnected-(X1-PadID)") (class "Default")
      (node (ref "X1") (pin "ID") (pinfunction "ID_ID") (pintype "bidirectional"))
    )
  )
)
